# esp32_pico_d4_motor_driver.net
KiCad netlist of a schematic drawn in Altium Designer
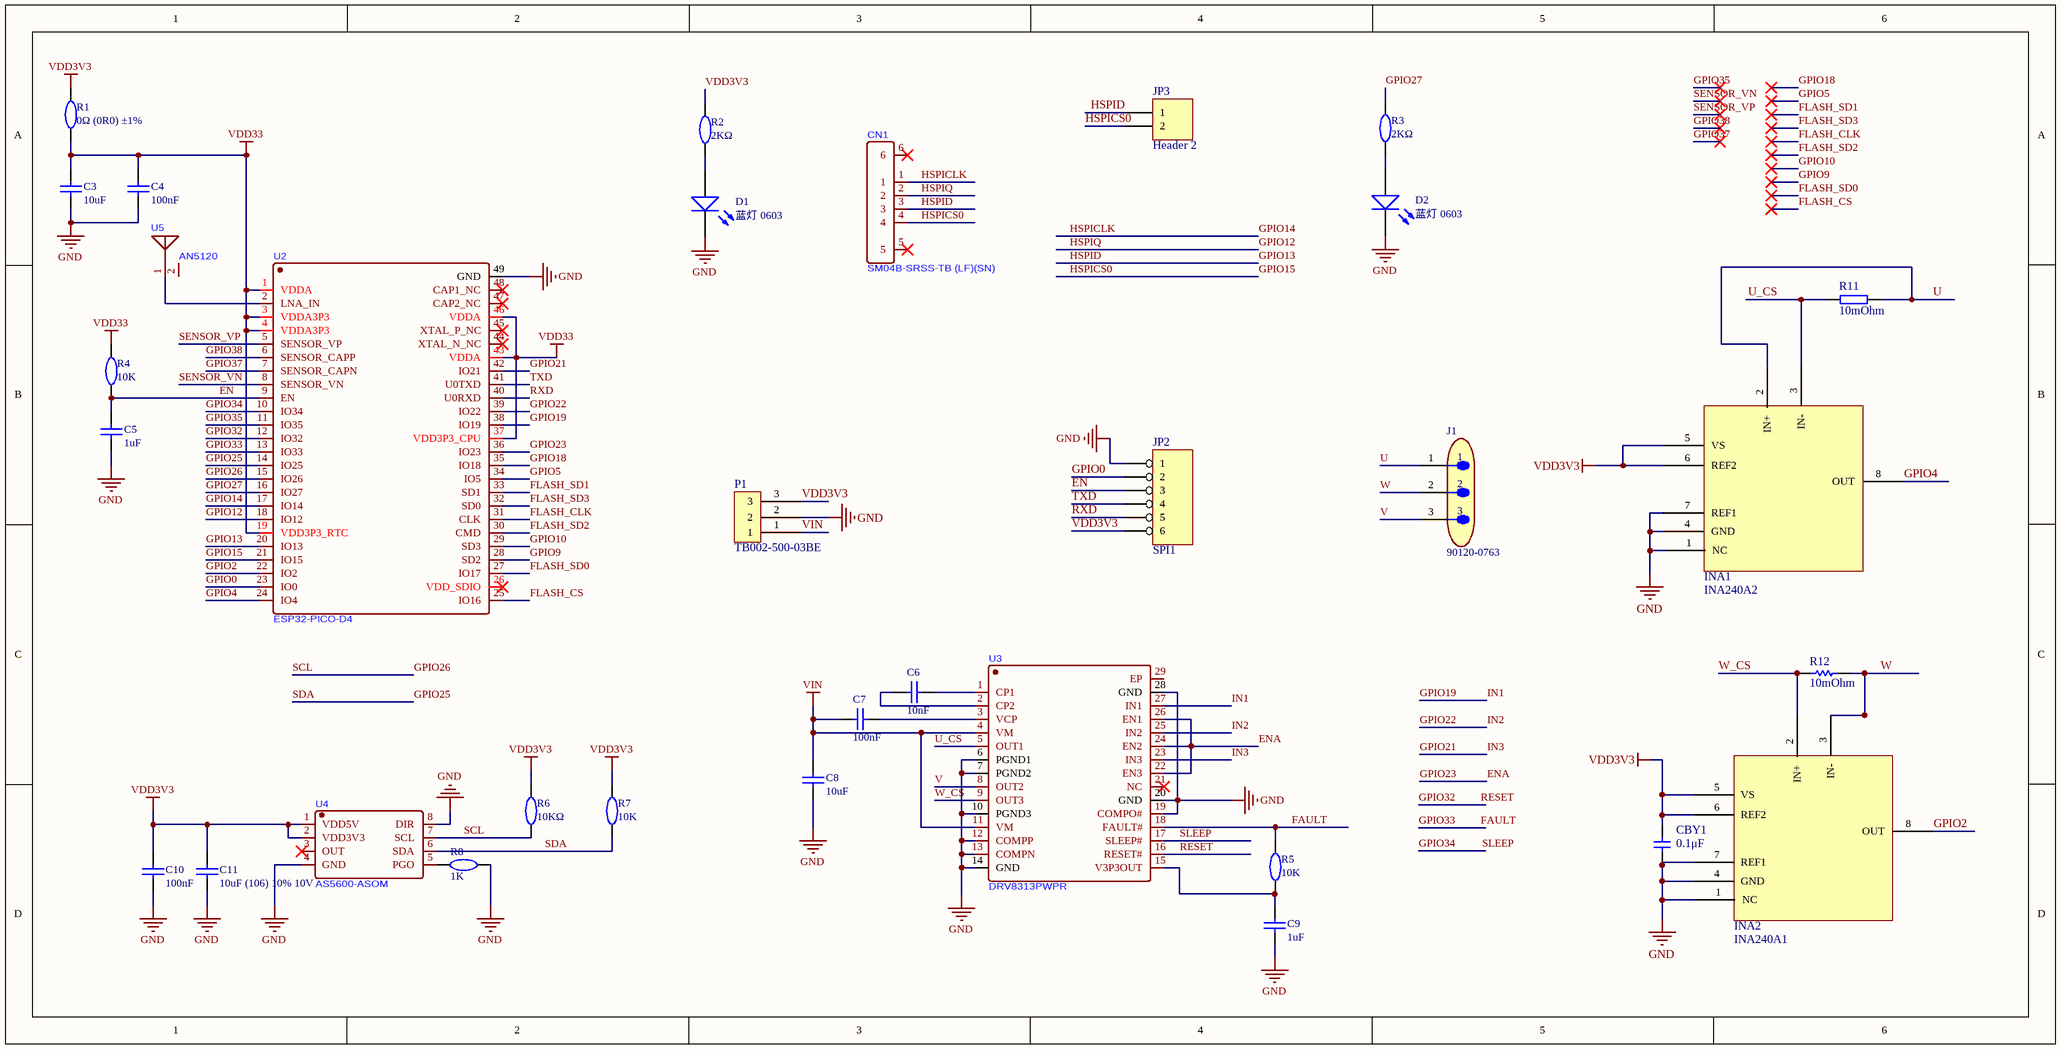
[diagram p0: esp32_pico_d4_motor_driver.SchDoc_2022-05-04 (1).schdoc]

(export (version "E")
  (design (tool "Eeschema 10.0.6"))
  (components
    (comp (ref "C3")
      (value "10uF")
      (footprint "0603C")
      (libsource (lib "altium-import") (part "root_1_10uF_"))
    )
    (comp (ref "C4")
      (value "100nF")
      (footprint "0603C")
      (libsource (lib "altium-import") (part "root_1_100nF_"))
    )
    (comp (ref "C5") (value "1uF") (footprint "0603C") (libsource (lib "altium-import") (part "root_1_1uF_")))
    (comp (ref "C6")
      (value "10nF")
      (footprint "0603C")
      (libsource (lib "altium-import") (part "root_0_10nF_"))
    )
    (comp (ref "C7")
      (value "100nF")
      (footprint "0603C")
      (libsource (lib "altium-import") (part "root_2_100nF_"))
    )
    (comp (ref "C8")
      (value "10uF")
      (footprint "0603C")
      (libsource (lib "altium-import") (part "root_1_10uF_"))
    )
    (comp (ref "C9") (value "1uF") (footprint "0603C") (libsource (lib "altium-import") (part "root_1_1uF_")))
    (comp (ref "C10")
      (value "100nF")
      (footprint "0603C")
      (libsource (lib "altium-import") (part "root_1_100nF_"))
    )
    (comp (ref "C11")
      (value "10uF (106) 10% 10V")
      (footprint "0603C")
      (libsource (lib "altium-import") (part "root_1_10uF (106) 10% 10V_"))
    )
    (comp (ref "CBY1") (value "0.1μF") (footprint "0603C") (libsource (lib "刘涛20200314") (part "CAP_1")))
    (comp (ref "CN1")
      (value "SM04B-SRSS-TB (LF)(SN)")
      (footprint "CONN-SMD_4P-P1.00_SM04B-SRSS-TB-LF-SN")
      (libsource (lib "altium-import") (part "root_3_SM04B-SRSS-TB (LF)(SN)_"))
    )
    (comp (ref "D1")
      (value "蓝灯 0603")
      (footprint "0603_diode")
      (libsource (lib "altium-import") (part "root_3_蓝灯 0603_"))
    )
    (comp (ref "D2")
      (value "蓝灯 0603")
      (footprint "0603_diode")
      (libsource (lib "altium-import") (part "root_3_蓝灯 0603_"))
    )
    (comp (ref "INA1") (value "INA240A2") (footprint "INA240") (libsource (lib "ArduinoFOC") (part "INA240")))
    (comp (ref "INA2") (value "INA240A1") (footprint "INA240") (libsource (lib "ArduinoFOC") (part "INA240")))
    (comp (ref "J1")
      (value "90120-0763")
      (footprint "10.7MHZ")
      (fields
        (field (name "MANUFACTURER") "Molex")
        (field (name "OCTOPART") "https://octopart.com/90120-0763-molex-655433")
      )
      (libsource (lib "altium-import") (part "root_0_90120-0763_"))
    )
    (comp (ref "JP2") (value "SPI1") (footprint "SHDR6") (libsource (lib "刘涛20200314") (part "HEADER 6")))
    (comp (ref "JP3")
      (value "Header 2")
      (footprint "SHDR2")
      (description "Header, 2-Pin")
      (fields (field (name "PUBLISHER") "Altium Limited"))
      (libsource (lib "Miscellaneous Connectors") (part "Header 2"))
    )
    (comp (ref "P1")
      (value "TB002-500-03BE")
      (footprint "SHDR3")
      (libsource (lib "ArduinoFOC") (part "TB002-500-03BE"))
    )
    (comp (ref "R1")
      (value "0Ω (0R0) ±1%")
      (footprint "0603R")
      (libsource (lib "altium-import") (part "root_1_0Ω (0R0) ±1%_"))
    )
    (comp (ref "R2") (value "2KΩ") (footprint "0603R") (libsource (lib "altium-import") (part "root_1_2KΩ_")))
    (comp (ref "R3") (value "2KΩ") (footprint "0603R") (libsource (lib "altium-import") (part "root_1_2KΩ_")))
    (comp (ref "R4") (value "10K") (footprint "0603R") (libsource (lib "altium-import") (part "root_1_10K_")))
    (comp (ref "R5") (value "10K") (footprint "0603R") (libsource (lib "altium-import") (part "root_1_10K_")))
    (comp (ref "R6")
      (value "10KΩ")
      (footprint "0603")
      (libsource (lib "altium-import") (part "root_1_10KΩ_"))
    )
    (comp (ref "R7") (value "10K") (footprint "0603R") (libsource (lib "altium-import") (part "root_1_10K_")))
    (comp (ref "R8") (value "1K") (footprint "0603") (libsource (lib "altium-import") (part "root_0_1K_")))
    (comp (ref "R11") (value "10mOhm") (footprint "RESC6332") (libsource (lib "刘涛20200314") (part "RES2")))
    (comp (ref "R12")
      (value "10mOhm")
      (footprint "RESC6332")
      (description "Resistor")
      (fields (field (name "PUBLISHER") "Altium Limited"))
      (libsource (lib "MB1137") (part "Res1"))
    )
    (comp (ref "U2")
      (value "ESP32-PICO-D4")
      (footprint "QFN-48_L7.0-W7.0-P0.50-BL-EP5.4")
      (libsource (lib "altium-import") (part "root_0_ESP32-PICO-D4_"))
    )
    (comp (ref "U3")
      (value "DRV8313PWPR")
      (footprint "HTSSOP-28_L9.8-W4.5-P0.65-LS6.6-BL-EP")
      (libsource (lib "altium-import") (part "root_0_DRV8313PWPR_"))
    )
    (comp (ref "U4")
      (value "AS5600-ASOM")
      (footprint "SOIC-8_L5.0-W4.0-P1.27-LS6.0-BL")
      (libsource (lib "altium-import") (part "root_0_AS5600-ASOM_"))
    )
    (comp (ref "U5")
      (value "AN5120")
      (footprint "ANT-SMD_L5.5-W2.0")
      (libsource (lib "altium-import") (part "root_0_AN5120_"))
    )
  )
  (nets
    (net (code "1") (name "/EN") (class "Default")
      (node (ref "C5") (pin "2") (pinfunction "2_2") (pintype "passive"))
      (node (ref "JP2") (pin "3") (pinfunction "3_3") (pintype "passive"))
      (node (ref "R4") (pin "1") (pinfunction "1_1") (pintype "passive"))
      (node (ref "U2") (pin "9") (pinfunction "EN_9") (pintype "passive"))
    )
    (net (code "2") (name "/ENA") (class "Default")
      (node (ref "U2") (pin "36") (pinfunction "IO23_36") (pintype "passive"))
      (node (ref "U3") (pin "22") (pinfunction "EN3_22") (pintype "passive"))
      (node (ref "U3") (pin "24") (pinfunction "EN2_24") (pintype "passive"))
      (node (ref "U3") (pin "26") (pinfunction "EN1_26") (pintype "passive"))
    )
    (net (code "3") (name "/FAULT") (class "Default")
      (node (ref "R5") (pin "2") (pinfunction "2_2") (pintype "passive"))
      (node (ref "U2") (pin "13") (pinfunction "IO33_13") (pintype "passive"))
      (node (ref "U3") (pin "18") (pinfunction "FAULT#_18") (pintype "passive"))
    )
    (net (code "4") (name "/FLASH_CLK") (class "Default")
      (node (ref "U2") (pin "31") (pinfunction "CLK_31") (pintype "passive"))
    )
    (net (code "5") (name "/FLASH_CS") (class "Default")
      (node (ref "U2") (pin "25") (pinfunction "IO16_25") (pintype "passive"))
    )
    (net (code "6") (name "/FLASH_SD0") (class "Default")
      (node (ref "U2") (pin "27") (pinfunction "IO17_27") (pintype "passive"))
    )
    (net (code "7") (name "/FLASH_SD1") (class "Default")
      (node (ref "U2") (pin "33") (pinfunction "SD1_33") (pintype "passive"))
    )
    (net (code "8") (name "/FLASH_SD2") (class "Default")
      (node (ref "U2") (pin "30") (pinfunction "CMD_30") (pintype "passive"))
    )
    (net (code "9") (name "/FLASH_SD3") (class "Default")
      (node (ref "U2") (pin "32") (pinfunction "SD0_32") (pintype "passive"))
    )
    (net (code "10") (name "/GPIO0") (class "Default")
      (node (ref "JP2") (pin "2") (pinfunction "2_2") (pintype "passive"))
      (node (ref "U2") (pin "23") (pinfunction "IO0_23") (pintype "passive"))
    )
    (net (code "11") (name "/GPIO2") (class "Default")
      (node (ref "INA2") (pin "8") (pinfunction "OUT_8") (pintype "passive"))
      (node (ref "U2") (pin "22") (pinfunction "IO2_22") (pintype "passive"))
    )
    (net (code "12") (name "/GPIO4") (class "Default")
      (node (ref "INA1") (pin "8") (pinfunction "OUT_8") (pintype "passive"))
      (node (ref "U2") (pin "24") (pinfunction "IO4_24") (pintype "passive"))
    )
    (net (code "13") (name "/GPIO5") (class "Default")
      (node (ref "U2") (pin "34") (pinfunction "IO5_34") (pintype "passive"))
    )
    (net (code "14") (name "/GPIO9") (class "Default")
      (node (ref "U2") (pin "28") (pinfunction "SD2_28") (pintype "passive"))
    )
    (net (code "15") (name "/GPIO10") (class "Default")
      (node (ref "U2") (pin "29") (pinfunction "SD3_29") (pintype "passive"))
    )
    (net (code "16") (name "/GPIO12") (class "Default")
      (node (ref "CN1") (pin "2") (pinfunction "2_2") (pintype "passive"))
      (node (ref "U2") (pin "18") (pinfunction "IO12_18") (pintype "passive"))
    )
    (net (code "17") (name "/GPIO13") (class "Default")
      (node (ref "CN1") (pin "3") (pinfunction "3_3") (pintype "passive"))
      (node (ref "JP3") (pin "2") (pinfunction "1_2") (pintype "passive"))
      (node (ref "U2") (pin "20") (pinfunction "IO13_20") (pintype "passive"))
    )
    (net (code "18") (name "/GPIO14") (class "Default")
      (node (ref "CN1") (pin "1") (pinfunction "1_1") (pintype "passive"))
      (node (ref "U2") (pin "17") (pinfunction "IO14_17") (pintype "passive"))
    )
    (net (code "19") (name "/GPIO15") (class "Default")
      (node (ref "CN1") (pin "4") (pinfunction "4_4") (pintype "passive"))
      (node (ref "JP3") (pin "1") (pinfunction "2_1") (pintype "passive"))
      (node (ref "U2") (pin "21") (pinfunction "IO15_21") (pintype "passive"))
    )
    (net (code "20") (name "/GPIO18") (class "Default")
      (node (ref "U2") (pin "35") (pinfunction "IO18_35") (pintype "passive"))
    )
    (net (code "21") (name "/GPIO19") (class "Default")
      (node (ref "U2") (pin "38") (pinfunction "IO19_38") (pintype "passive"))
      (node (ref "U3") (pin "27") (pinfunction "IN1_27") (pintype "passive"))
    )
    (net (code "22") (name "/GPIO21") (class "Default")
      (node (ref "U2") (pin "42") (pinfunction "IO21_42") (pintype "passive"))
      (node (ref "U3") (pin "23") (pinfunction "IN3_23") (pintype "passive"))
    )
    (net (code "23") (name "/GPIO22") (class "Default")
      (node (ref "U2") (pin "39") (pinfunction "IO22_39") (pintype "passive"))
      (node (ref "U3") (pin "25") (pinfunction "IN2_25") (pintype "passive"))
    )
    (net (code "24") (name "/GPIO25") (class "Default")
      (node (ref "R7") (pin "1") (pinfunction "1_1") (pintype "passive"))
      (node (ref "U2") (pin "14") (pinfunction "IO25_14") (pintype "passive"))
      (node (ref "U4") (pin "6") (pinfunction "SDA_6") (pintype "passive"))
    )
    (net (code "25") (name "/GPIO26") (class "Default")
      (node (ref "R6") (pin "1") (pinfunction "1_1") (pintype "passive"))
      (node (ref "U2") (pin "15") (pinfunction "IO26_15") (pintype "passive"))
      (node (ref "U4") (pin "7") (pinfunction "SCL_7") (pintype "passive"))
    )
    (net (code "26") (name "/GPIO27") (class "Default")
      (node (ref "R3") (pin "2") (pinfunction "2_2") (pintype "passive"))
      (node (ref "U2") (pin "16") (pinfunction "IO27_16") (pintype "passive"))
    )
    (net (code "27") (name "/GPIO32") (class "Default")
      (node (ref "U2") (pin "12") (pinfunction "IO32_12") (pintype "passive"))
      (node (ref "U3") (pin "16") (pinfunction "RESET#_16") (pintype "passive"))
    )
    (net (code "28") (name "/GPIO34") (class "Default")
      (node (ref "U2") (pin "10") (pinfunction "IO34_10") (pintype "passive"))
      (node (ref "U3") (pin "17") (pinfunction "SLEEP#_17") (pintype "passive"))
    )
    (net (code "29") (name "/GPIO35") (class "Default")
      (node (ref "U2") (pin "11") (pinfunction "IO35_11") (pintype "passive"))
    )
    (net (code "30") (name "/GPIO37") (class "Default")
      (node (ref "U2") (pin "7") (pinfunction "SENSOR_CAPN_7") (pintype "passive"))
    )
    (net (code "31") (name "/GPIO38") (class "Default")
      (node (ref "U2") (pin "6") (pinfunction "SENSOR_CAPP_6") (pintype "passive"))
    )
    (net (code "32") (name "/RXD") (class "Default")
      (node (ref "JP2") (pin "5") (pinfunction "5_5") (pintype "passive"))
      (node (ref "U2") (pin "40") (pinfunction "U0RXD_40") (pintype "passive"))
    )
    (net (code "33") (name "/SENSOR_VN") (class "Default")
      (node (ref "U2") (pin "8") (pinfunction "SENSOR_VN_8") (pintype "passive"))
    )
    (net (code "34") (name "/SENSOR_VP") (class "Default")
      (node (ref "U2") (pin "5") (pinfunction "SENSOR_VP_5") (pintype "passive"))
    )
    (net (code "35") (name "/TXD") (class "Default")
      (node (ref "JP2") (pin "4") (pinfunction "4_4") (pintype "passive"))
      (node (ref "U2") (pin "41") (pinfunction "U0TXD_41") (pintype "passive"))
    )
    (net (code "36") (name "/U") (class "Default")
      (node (ref "INA1") (pin "2") (pinfunction "IN+_2") (pintype "passive"))
      (node (ref "J1") (pin "1") (pinfunction "1_1") (pintype "passive"))
      (node (ref "R11") (pin "2") (pinfunction "2_2") (pintype "passive"))
    )
    (net (code "37") (name "/U_CS") (class "Default")
      (node (ref "INA1") (pin "3") (pinfunction "IN-_3") (pintype "passive"))
      (node (ref "R11") (pin "1") (pinfunction "1_1") (pintype "passive"))
      (node (ref "U3") (pin "5") (pinfunction "OUT1_5") (pintype "passive"))
    )
    (net (code "38") (name "/V") (class "Default")
      (node (ref "J1") (pin "3") (pinfunction "3_3") (pintype "passive"))
      (node (ref "U3") (pin "8") (pinfunction "OUT2_8") (pintype "passive"))
    )
    (net (code "39") (name "/W") (class "Default")
      (node (ref "INA2") (pin "3") (pinfunction "IN-_3") (pintype "passive"))
      (node (ref "J1") (pin "2") (pinfunction "2_2") (pintype "passive"))
      (node (ref "R12") (pin "2") (pinfunction "2_2") (pintype "passive"))
    )
    (net (code "40") (name "/W_CS") (class "Default")
      (node (ref "INA2") (pin "2") (pinfunction "IN+_2") (pintype "passive"))
      (node (ref "R12") (pin "1") (pinfunction "1_1") (pintype "passive"))
      (node (ref "U3") (pin "9") (pinfunction "OUT3_9") (pintype "passive"))
    )
    (net (code "41") (name "GND") (class "Default")
      (node (ref "C10") (pin "1") (pinfunction "1_1") (pintype "passive"))
      (node (ref "C11") (pin "1") (pinfunction "1_1") (pintype "passive"))
      (node (ref "C3") (pin "1") (pinfunction "1_1") (pintype "passive"))
      (node (ref "C4") (pin "1") (pinfunction "1_1") (pintype "passive"))
      (node (ref "C5") (pin "1") (pinfunction "1_1") (pintype "passive"))
      (node (ref "C8") (pin "1") (pinfunction "1_1") (pintype "passive"))
      (node (ref "C9") (pin "1") (pinfunction "1_1") (pintype "passive"))
      (node (ref "CBY1") (pin "2") (pintype "passive"))
      (node (ref "D1") (pin "K") (pinfunction "K_K") (pintype "passive"))
      (node (ref "D2") (pin "K") (pinfunction "K_K") (pintype "passive"))
      (node (ref "INA1") (pin "1") (pinfunction "NC_1") (pintype "passive"))
      (node (ref "INA1") (pin "4") (pinfunction "GND_4") (pintype "passive"))
      (node (ref "INA1") (pin "7") (pinfunction "REF1_7") (pintype "passive"))
      (node (ref "INA2") (pin "1") (pinfunction "NC_1") (pintype "passive"))
      (node (ref "INA2") (pin "4") (pinfunction "GND_4") (pintype "passive"))
      (node (ref "INA2") (pin "7") (pinfunction "REF1_7") (pintype "passive"))
      (node (ref "JP2") (pin "1") (pinfunction "1_1") (pintype "passive"))
      (node (ref "P1") (pin "2") (pinfunction "2_2") (pintype "passive"))
      (node (ref "R8") (pin "2") (pinfunction "2_2") (pintype "passive"))
      (node (ref "U2") (pin "49") (pinfunction "GND_49") (pintype "passive"))
      (node (ref "U3") (pin "10") (pinfunction "PGND3_10") (pintype "passive"))
      (node (ref "U3") (pin "12") (pinfunction "COMPP_12") (pintype "passive"))
      (node (ref "U3") (pin "13") (pinfunction "COMPN_13") (pintype "passive"))
      (node (ref "U3") (pin "14") (pinfunction "GND_14") (pintype "passive"))
      (node (ref "U3") (pin "19") (pinfunction "COMPO#_19") (pintype "passive"))
      (node (ref "U3") (pin "20") (pinfunction "GND_20") (pintype "passive"))
      (node (ref "U3") (pin "28") (pinfunction "GND_28") (pintype "passive"))
      (node (ref "U3") (pin "6") (pinfunction "PGND1_6") (pintype "passive"))
      (node (ref "U3") (pin "7") (pinfunction "PGND2_7") (pintype "passive"))
      (node (ref "U4") (pin "4") (pinfunction "GND_4") (pintype "passive"))
      (node (ref "U4") (pin "8") (pinfunction "DIR_8") (pintype "passive"))
    )
    (net (code "42") (name "Net-(D1-PadA)") (class "Default")
      (node (ref "D1") (pin "A") (pinfunction "A_A") (pintype "passive"))
      (node (ref "R2") (pin "1") (pinfunction "1_1") (pintype "passive"))
    )
    (net (code "43") (name "Net-(D2-PadA)") (class "Default")
      (node (ref "D2") (pin "A") (pinfunction "A_A") (pintype "passive"))
      (node (ref "R3") (pin "1") (pinfunction "1_1") (pintype "passive"))
    )
    (net (code "44") (name "Net-(U2-LNA_IN)") (class "Default")
      (node (ref "U2") (pin "2") (pinfunction "LNA_IN_2") (pintype "passive"))
      (node (ref "U5") (pin "1") (pinfunction "1_1") (pintype "passive"))
    )
    (net (code "45") (name "Net-(U3-CP1)") (class "Default")
      (node (ref "C6") (pin "2") (pinfunction "2_2") (pintype "passive"))
      (node (ref "U3") (pin "1") (pinfunction "CP1_1") (pintype "passive"))
    )
    (net (code "46") (name "Net-(U3-CP2)") (class "Default")
      (node (ref "C6") (pin "1") (pinfunction "1_1") (pintype "passive"))
      (node (ref "U3") (pin "2") (pinfunction "CP2_2") (pintype "passive"))
    )
    (net (code "47") (name "Net-(U3-V3P3OUT)") (class "Default")
      (node (ref "C9") (pin "2") (pinfunction "2_2") (pintype "passive"))
      (node (ref "R5") (pin "1") (pinfunction "1_1") (pintype "passive"))
      (node (ref "U3") (pin "15") (pinfunction "V3P3OUT_15") (pintype "passive"))
    )
    (net (code "48") (name "Net-(U3-VCP)") (class "Default")
      (node (ref "C7") (pin "1") (pinfunction "1_1") (pintype "passive"))
      (node (ref "U3") (pin "3") (pinfunction "VCP_3") (pintype "passive"))
    )
    (net (code "49") (name "Net-(U4-PGO)") (class "Default")
      (node (ref "R8") (pin "1") (pinfunction "1_1") (pintype "passive"))
      (node (ref "U4") (pin "5") (pinfunction "PGO_5") (pintype "passive"))
    )
    (net (code "50") (name "VDD3V3") (class "Default")
      (node (ref "C10") (pin "2") (pinfunction "2_2") (pintype "passive"))
      (node (ref "C11") (pin "2") (pinfunction "2_2") (pintype "passive"))
      (node (ref "CBY1") (pin "1") (pintype "passive"))
      (node (ref "INA1") (pin "5") (pinfunction "VS_5") (pintype "passive"))
      (node (ref "INA1") (pin "6") (pinfunction "REF2_6") (pintype "passive"))
      (node (ref "INA2") (pin "5") (pinfunction "VS_5") (pintype "passive"))
      (node (ref "INA2") (pin "6") (pinfunction "REF2_6") (pintype "passive"))
      (node (ref "JP2") (pin "6") (pinfunction "6_6") (pintype "passive"))
      (node (ref "P1") (pin "3") (pinfunction "3_3") (pintype "passive"))
      (node (ref "R1") (pin "2") (pinfunction "2_2") (pintype "passive"))
      (node (ref "R2") (pin "2") (pinfunction "2_2") (pintype "passive"))
      (node (ref "R6") (pin "2") (pinfunction "2_2") (pintype "passive"))
      (node (ref "R7") (pin "2") (pinfunction "2_2") (pintype "passive"))
      (node (ref "U4") (pin "1") (pinfunction "VDD5V_1") (pintype "passive"))
      (node (ref "U4") (pin "2") (pinfunction "VDD3V3_2") (pintype "passive"))
    )
    (net (code "51") (name "VDD33") (class "Default")
      (node (ref "C3") (pin "2") (pinfunction "2_2") (pintype "passive"))
      (node (ref "C4") (pin "2") (pinfunction "2_2") (pintype "passive"))
      (node (ref "R1") (pin "1") (pinfunction "1_1") (pintype "passive"))
      (node (ref "R4") (pin "2") (pinfunction "2_2") (pintype "passive"))
      (node (ref "U2") (pin "1") (pinfunction "VDDA_1") (pintype "passive"))
      (node (ref "U2") (pin "19") (pinfunction "VDD3P3_RTC_19") (pintype "passive"))
      (node (ref "U2") (pin "3") (pinfunction "VDDA3P3_3") (pintype "passive"))
      (node (ref "U2") (pin "37") (pinfunction "VDD3P3_CPU_37") (pintype "passive"))
      (node (ref "U2") (pin "4") (pinfunction "VDDA3P3_4") (pintype "passive"))
      (node (ref "U2") (pin "43") (pinfunction "VDDA_43") (pintype "passive"))
      (node (ref "U2") (pin "46") (pinfunction "VDDA_46") (pintype "passive"))
    )
    (net (code "52") (name "VIN") (class "Default")
      (node (ref "C7") (pin "2") (pinfunction "2_2") (pintype "passive"))
      (node (ref "C8") (pin "2") (pinfunction "2_2") (pintype "passive"))
      (node (ref "P1") (pin "1") (pinfunction "1_1") (pintype "passive"))
      (node (ref "U3") (pin "11") (pinfunction "VM_11") (pintype "passive"))
      (node (ref "U3") (pin "4") (pinfunction "VM_4") (pintype "passive"))
    )
    (net (code "53") (name "unconnected-(CN1-Pad5)") (class "Default")
      (node (ref "CN1") (pin "5") (pinfunction "5_5") (pintype "passive+no_connect"))
    )
    (net (code "54") (name "unconnected-(CN1-Pad6)") (class "Default")
      (node (ref "CN1") (pin "6") (pinfunction "6_6") (pintype "passive+no_connect"))
    )
    (net (code "55") (name "unconnected-(U2-CAP1_NC-Pad48)") (class "Default")
      (node (ref "U2") (pin "48") (pinfunction "CAP1_NC_48") (pintype "passive+no_connect"))
    )
    (net (code "56") (name "unconnected-(U2-CAP2_NC-Pad47)") (class "Default")
      (node (ref "U2") (pin "47") (pinfunction "CAP2_NC_47") (pintype "passive+no_connect"))
    )
    (net (code "57") (name "unconnected-(U2-VDD_SDIO-Pad26)") (class "Default")
      (node (ref "U2") (pin "26") (pinfunction "VDD_SDIO_26") (pintype "passive+no_connect"))
    )
    (net (code "58") (name "unconnected-(U2-XTAL_N_NC-Pad44)") (class "Default")
      (node (ref "U2") (pin "44") (pinfunction "XTAL_N_NC_44") (pintype "passive+no_connect"))
    )
    (net (code "59") (name "unconnected-(U2-XTAL_P_NC-Pad45)") (class "Default")
      (node (ref "U2") (pin "45") (pinfunction "XTAL_P_NC_45") (pintype "passive+no_connect"))
    )
    (net (code "60") (name "unconnected-(U3-EP-Pad29)") (class "Default")
      (node (ref "U3") (pin "29") (pinfunction "EP_29") (pintype "passive"))
    )
    (net (code "61") (name "unconnected-(U3-NC-Pad21)") (class "Default")
      (node (ref "U3") (pin "21") (pinfunction "NC_21") (pintype "passive+no_connect"))
    )
    (net (code "62") (name "unconnected-(U4-OUT-Pad3)") (class "Default")
      (node (ref "U4") (pin "3") (pinfunction "OUT_3") (pintype "passive+no_connect"))
    )
    (net (code "63") (name "unconnected-(U5-NC-Pad2)") (class "Default")
      (node (ref "U5") (pin "2") (pinfunction "NC_2") (pintype "passive"))
    )
  )
)
